# powersupply_grid8_0.net
KiCad netlist of a schematic drawn in Altium Designer
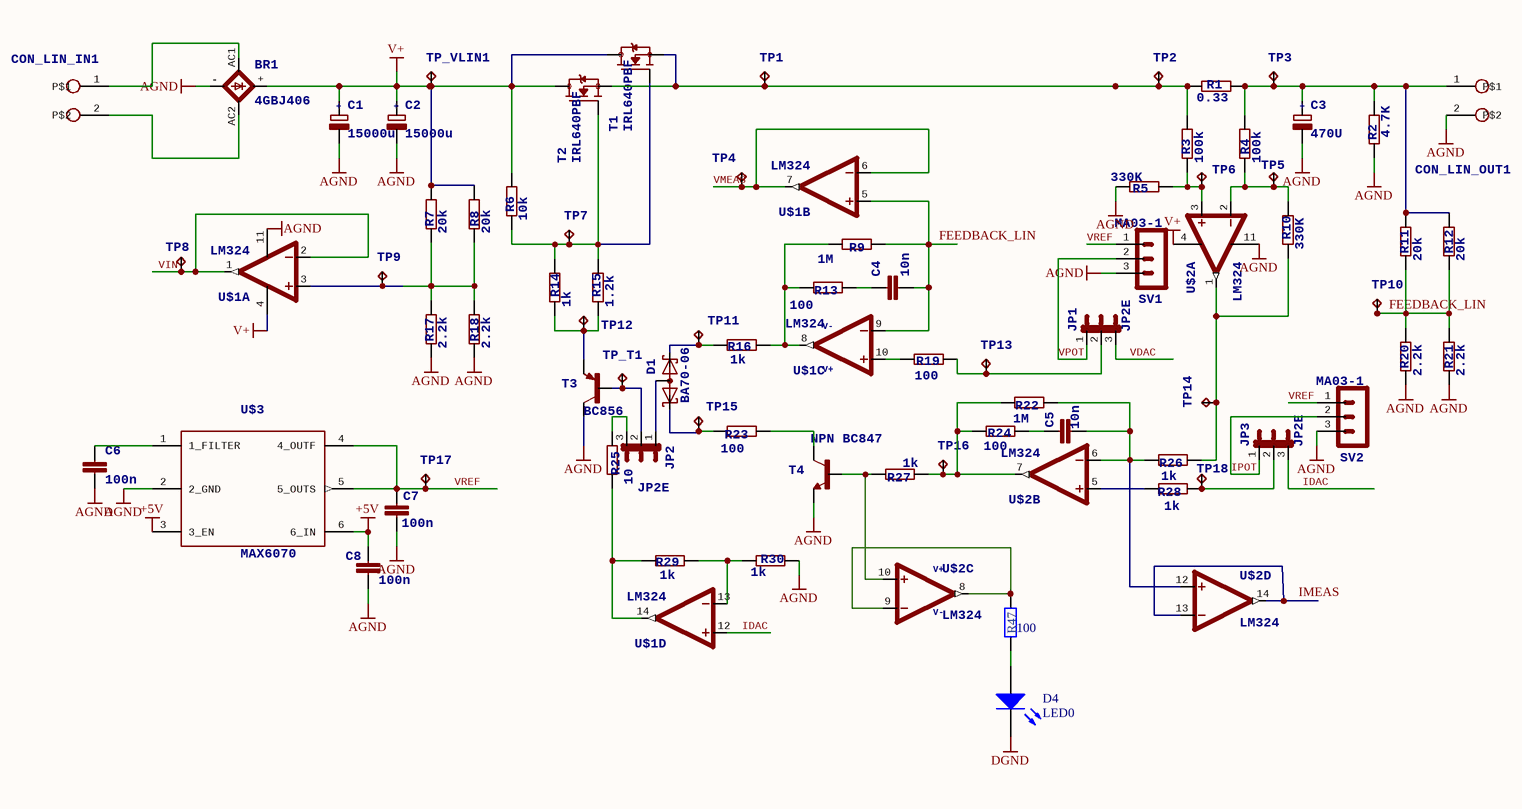
[diagram p0: powersupply_grid8_0.SchDoc]

(export (version "E")
  (design (tool "Eeschema 10.0.6"))
  (components
    (comp (ref "BR1") (value "4GBJ406") (footprint "FB100") (libsource (lib "4GBJ406F") (part "4GBJ406")))
    (comp (ref "C1")
      (value "15000u")
      (footprint "EB30D")
      (description "<B>POLARIZED CAPACITOR</B>, European symbol")
      (fields (field (name "+") "+"))
      (libsource (lib "rcl") (part "CPOL-EUE10-30"))
    )
    (comp (ref "C2")
      (value "15000u")
      (footprint "EB30D")
      (description "<B>POLARIZED CAPACITOR</B>, European symbol")
      (fields (field (name "+") "+"))
      (libsource (lib "rcl") (part "CPOL-EUE10-30"))
    )
    (comp (ref "C3")
      (value "470U")
      (footprint "E5-13")
      (description "<B>POLARIZED CAPACITOR</B>, European symbol")
      (fields (field (name "+") "+"))
      (libsource (lib "rcl") (part "CPOL-EUE5-13"))
    )
    (comp (ref "C4")
      (value "10n")
      (footprint "C0805")
      (description "<B>CAPACITOR</B>, European symbol")
      (libsource (lib "rcl") (part "C-EUC0805"))
    )
    (comp (ref "C5")
      (value "10n")
      (footprint "C0805")
      (description "<B>CAPACITOR</B>, European symbol")
      (libsource (lib "rcl") (part "C-EUC0805"))
    )
    (comp (ref "C6")
      (value "100n")
      (footprint "C0402")
      (description "<B>CAPACITOR</B>, European symbol")
      (libsource (lib "rcl") (part "C-EUC0402"))
    )
    (comp (ref "C7")
      (value "100n")
      (footprint "C0402")
      (description "<B>CAPACITOR</B>, European symbol")
      (libsource (lib "rcl") (part "C-EUC0402"))
    )
    (comp (ref "C8")
      (value "100n")
      (footprint "C0402")
      (description "<B>CAPACITOR</B>, European symbol")
      (libsource (lib "rcl") (part "C-EUC0402"))
    )
    (comp (ref "CON_LIN_IN1")
      (value "POWERCON")
      (footprint "MKS1852-6-0-202")
      (libsource (lib "powercon") (part "POWERCON"))
    )
    (comp (ref "CON_LIN_OUT1")
      (value "POWERCON")
      (footprint "MKS1852-6-0-202")
      (libsource (lib "powercon") (part "POWERCON"))
    )
    (comp (ref "D1") (value "BA70-06") (footprint "SOT23") (libsource (lib "diode") (part "BAS40-06")))
    (comp (ref "D4")
      (value "LED0")
      (footprint "LED-0")
      (description "Typical INFRARED GaAs LED")
      (fields (field (name "PUBLISHER") "Altium Limited"))
      (libsource (lib "Miscellaneous Devices") (part "LED0"))
    )
    (comp (ref "JP1")
      (value "JP2E")
      (footprint "JP2")
      (description "<b>JUMPER</b>")
      (libsource (lib "jumper") (part "JP2E"))
    )
    (comp (ref "JP2")
      (value "JP2E")
      (footprint "JP2")
      (description "<b>JUMPER</b>")
      (libsource (lib "jumper") (part "JP2E"))
    )
    (comp (ref "JP3")
      (value "JP2E")
      (footprint "JP2")
      (description "<b>JUMPER</b>")
      (libsource (lib "jumper") (part "JP2E"))
    )
    (comp (ref "R1")
      (value "0.33")
      (footprint "R2010")
      (description "<B>RESISTOR</B>, European symbol")
      (libsource (lib "rcl") (part "R-EU_R2010"))
    )
    (comp (ref "R2")
      (value "4.7K")
      (footprint "R2512")
      (description "<B>RESISTOR</B>, European symbol")
      (libsource (lib "rcl") (part "R-EU_R2512"))
    )
    (comp (ref "R3")
      (value "100k")
      (footprint "R0805")
      (description "<B>RESISTOR</B>, European symbol")
      (libsource (lib "rcl") (part "R-EU_R0805"))
    )
    (comp (ref "R4")
      (value "100k")
      (footprint "R0805")
      (description "<B>RESISTOR</B>, European symbol")
      (libsource (lib "rcl") (part "R-EU_R0805"))
    )
    (comp (ref "R5")
      (value "330K")
      (footprint "R0805")
      (description "<B>RESISTOR</B>, European symbol")
      (libsource (lib "rcl") (part "R-EU_R0805"))
    )
    (comp (ref "R6")
      (value "10k")
      (footprint "R0805")
      (description "<B>RESISTOR</B>, European symbol")
      (libsource (lib "rcl") (part "R-EU_R0805"))
    )
    (comp (ref "R7")
      (value "20k")
      (footprint "R0805")
      (description "<B>RESISTOR</B>, European symbol")
      (libsource (lib "rcl") (part "R-EU_R0805"))
    )
    (comp (ref "R8")
      (value "20k")
      (footprint "R0805")
      (description "<B>RESISTOR</B>, European symbol")
      (libsource (lib "rcl") (part "R-EU_R0805"))
    )
    (comp (ref "R9")
      (value "1M")
      (footprint "R0805")
      (description "<B>RESISTOR</B>, European symbol")
      (libsource (lib "rcl") (part "R-EU_R0805"))
    )
    (comp (ref "R10")
      (value "330K")
      (footprint "R0805")
      (description "<B>RESISTOR</B>, European symbol")
      (libsource (lib "rcl") (part "R-EU_R0805"))
    )
    (comp (ref "R11")
      (value "20k")
      (footprint "R0805")
      (description "<B>RESISTOR</B>, European symbol")
      (libsource (lib "rcl") (part "R-EU_R0805"))
    )
    (comp (ref "R12")
      (value "20k")
      (footprint "R0805")
      (description "<B>RESISTOR</B>, European symbol")
      (libsource (lib "rcl") (part "R-EU_R0805"))
    )
    (comp (ref "R13")
      (value "100")
      (footprint "R0805")
      (description "<B>RESISTOR</B>, European symbol")
      (libsource (lib "rcl") (part "R-EU_R0805"))
    )
    (comp (ref "R14")
      (value "1k")
      (footprint "R0805")
      (description "<B>RESISTOR</B>, European symbol")
      (libsource (lib "rcl") (part "R-EU_R0805"))
    )
    (comp (ref "R15")
      (value "1.2k")
      (footprint "R0805")
      (description "<B>RESISTOR</B>, European symbol")
      (libsource (lib "rcl") (part "R-EU_R0805"))
    )
    (comp (ref "R16")
      (value "1k")
      (footprint "R0805")
      (description "<B>RESISTOR</B>, European symbol")
      (libsource (lib "rcl") (part "R-EU_R0805"))
    )
    (comp (ref "R17")
      (value "2.2k")
      (footprint "R0805")
      (description "<B>RESISTOR</B>, European symbol")
      (libsource (lib "rcl") (part "R-EU_R0805"))
    )
    (comp (ref "R18")
      (value "2.2k")
      (footprint "R0805")
      (description "<B>RESISTOR</B>, European symbol")
      (libsource (lib "rcl") (part "R-EU_R0805"))
    )
    (comp (ref "R19")
      (value "100")
      (footprint "R0805")
      (description "<B>RESISTOR</B>, European symbol")
      (libsource (lib "rcl") (part "R-EU_R0805"))
    )
    (comp (ref "R20")
      (value "2.2k")
      (footprint "R0805")
      (description "<B>RESISTOR</B>, European symbol")
      (libsource (lib "rcl") (part "R-EU_R0805"))
    )
    (comp (ref "R21")
      (value "2.2k")
      (footprint "R0805")
      (description "<B>RESISTOR</B>, European symbol")
      (libsource (lib "rcl") (part "R-EU_R0805"))
    )
    (comp (ref "R22")
      (value "1M")
      (footprint "R0805")
      (description "<B>RESISTOR</B>, European symbol")
      (libsource (lib "rcl") (part "R-EU_R0805"))
    )
    (comp (ref "R23")
      (value "100")
      (footprint "R0805")
      (description "<B>RESISTOR</B>, European symbol")
      (libsource (lib "rcl") (part "R-EU_R0805"))
    )
    (comp (ref "R24")
      (value "100")
      (footprint "R0805")
      (description "<B>RESISTOR</B>, European symbol")
      (libsource (lib "rcl") (part "R-EU_R0805"))
    )
    (comp (ref "R25")
      (value "10")
      (footprint "R0805")
      (description "<B>RESISTOR</B>, European symbol")
      (libsource (lib "rcl") (part "R-EU_R0805"))
    )
    (comp (ref "R26")
      (value "1k")
      (footprint "R0805")
      (description "<B>RESISTOR</B>, European symbol")
      (libsource (lib "rcl") (part "R-EU_R0805"))
    )
    (comp (ref "R27")
      (value "1k")
      (footprint "R0805")
      (description "<B>RESISTOR</B>, European symbol")
      (libsource (lib "rcl") (part "R-EU_R0805"))
    )
    (comp (ref "R28")
      (value "1k")
      (footprint "R0805")
      (description "<B>RESISTOR</B>, European symbol")
      (libsource (lib "rcl") (part "R-EU_R0805"))
    )
    (comp (ref "R29")
      (value "1k")
      (footprint "R0805")
      (description "<B>RESISTOR</B>, European symbol")
      (libsource (lib "rcl") (part "R-EU_R0805"))
    )
    (comp (ref "R30")
      (value "1k")
      (footprint "R0805")
      (description "<B>RESISTOR</B>, European symbol")
      (libsource (lib "rcl") (part "R-EU_R0805"))
    )
    (comp (ref "R47")
      (value "100")
      (footprint "6-0805_L")
      (description "Resistor")
      (fields (field (name "Comment") "Res2") (field (name "PUBLISHER") "Altium Limited"))
      (libsource (lib "Miscellaneous Devices") (part "Res2"))
    )
    (comp (ref "SV1")
      (value "MA03-1")
      (footprint "MA03-1")
      (description "<b>PIN HEADER</b>")
      (libsource (lib "con-lstb") (part "MA03-1"))
    )
    (comp (ref "SV2")
      (value "MA03-1")
      (footprint "MA03-1")
      (description "<b>PIN HEADER</b>")
      (libsource (lib "con-lstb") (part "MA03-1"))
    )
    (comp (ref "T1")
      (value "IRL640PBF")
      (footprint "TO-220AB")
      (libsource (lib "TO-220AB") (part "IRL640PBF"))
    )
    (comp (ref "T2")
      (value "IRL640PBF")
      (footprint "TO-220AB")
      (libsource (lib "TO-220AB") (part "IRL640PBF"))
    )
    (comp (ref "T3")
      (value "BC856")
      (footprint "SOT23-BEC")
      (description "PNP Transistror")
      (libsource (lib "transistor") (part "*-PNP-SOT23-BEC"))
    )
    (comp (ref "T4")
      (value "NPN BC847")
      (footprint "SOT23-BEC")
      (libsource (lib "transistor") (part "*-NPN-SOT23-BEC"))
    )
    (comp (ref "TP1")
      (value "TPB2,54")
      (footprint "B2,54")
      (description "<b>Test pad</b>")
      (libsource (lib "testpad") (part "TPB2,54"))
    )
    (comp (ref "TP2")
      (value "TPB2,54")
      (footprint "B2,54")
      (description "<b>Test pad</b>")
      (libsource (lib "testpad") (part "TPB2,54"))
    )
    (comp (ref "TP3")
      (value "TPB2,54")
      (footprint "B2,54")
      (description "<b>Test pad</b>")
      (libsource (lib "testpad") (part "TPB2,54"))
    )
    (comp (ref "TP4")
      (value "TPB2,54")
      (footprint "B2,54")
      (description "<b>Test pad</b>")
      (libsource (lib "testpad") (part "TPB2,54"))
    )
    (comp (ref "TP5")
      (value "TPB2,54")
      (footprint "B2,54")
      (description "<b>Test pad</b>")
      (libsource (lib "testpad") (part "TPB2,54"))
    )
    (comp (ref "TP6")
      (value "TPB2,54")
      (footprint "B2,54")
      (description "<b>Test pad</b>")
      (libsource (lib "testpad") (part "TPB2,54"))
    )
    (comp (ref "TP7")
      (value "TPB2,54")
      (footprint "B2,54")
      (description "<b>Test pad</b>")
      (libsource (lib "testpad") (part "TPB2,54"))
    )
    (comp (ref "TP8")
      (value "TPB2,54")
      (footprint "B2,54")
      (description "<b>Test pad</b>")
      (libsource (lib "testpad") (part "TPB2,54"))
    )
    (comp (ref "TP9")
      (value "TPB2,54")
      (footprint "B2,54")
      (description "<b>Test pad</b>")
      (libsource (lib "testpad") (part "TPB2,54"))
    )
    (comp (ref "TP10")
      (value "TPB2,54")
      (footprint "B2,54")
      (description "<b>Test pad</b>")
      (libsource (lib "testpad") (part "TPB2,54"))
    )
    (comp (ref "TP11")
      (value "TPB2,54")
      (footprint "B2,54")
      (description "<b>Test pad</b>")
      (libsource (lib "testpad") (part "TPB2,54"))
    )
    (comp (ref "TP12")
      (value "TPB2,54")
      (footprint "B2,54")
      (description "<b>Test pad</b>")
      (libsource (lib "testpad") (part "TPB2,54"))
    )
    (comp (ref "TP13")
      (value "TPB2,54")
      (footprint "B2,54")
      (description "<b>Test pad</b>")
      (libsource (lib "testpad") (part "TPB2,54"))
    )
    (comp (ref "TP14")
      (value "TPB2,54")
      (footprint "B2,54")
      (description "<b>Test pad</b>")
      (libsource (lib "testpad") (part "TPB2,54"))
    )
    (comp (ref "TP15")
      (value "TPB2,54")
      (footprint "B2,54")
      (description "<b>Test pad</b>")
      (libsource (lib "testpad") (part "TPB2,54"))
    )
    (comp (ref "TP16")
      (value "TPB2,54")
      (footprint "B2,54")
      (description "<b>Test pad</b>")
      (libsource (lib "testpad") (part "TPB2,54"))
    )
    (comp (ref "TP17")
      (value "TPB2,54")
      (footprint "B2,54")
      (description "<b>Test pad</b>")
      (libsource (lib "testpad") (part "TPB2,54"))
    )
    (comp (ref "TP18")
      (value "TPB2,54")
      (footprint "B2,54")
      (description "<b>Test pad</b>")
      (libsource (lib "testpad") (part "TPB2,54"))
    )
    (comp (ref "TP_T1")
      (value "TPB2,54")
      (footprint "B2,54")
      (description "<b>Test pad</b>")
      (libsource (lib "testpad") (part "TPB2,54"))
    )
    (comp (ref "TP_VLIN1")
      (value "TPB2,54")
      (footprint "B2,54")
      (description "<b>Test pad</b>")
      (libsource (lib "testpad") (part "TPB2,54"))
    )
    (comp (ref "U$1")
      (value "LM324")
      (footprint "SO14")
      (fields (field (name "V+") "V+") (field (name "V-") "V-"))
      (libsource (lib "lm324") (part "LM324"))
    )
    (comp (ref "U$2")
      (value "LM324")
      (footprint "SO14")
      (fields (field (name "V+") "V+") (field (name "V-") "V-"))
      (libsource (lib "lm324") (part "LM324"))
    )
    (comp (ref "U$3") (value "MAX6070") (footprint "SOT23-6") (libsource (lib "max6070") (part "MAX6070")))
  )
  (nets
    (net (code "1") (name "+5V") (class "Default")
      (node (ref "C8") (pin "1") (pinfunction "1_1") (pintype "passive"))
      (node (ref "U$3") (pin "3") (pinfunction "3_EN_3") (pintype "passive"))
      (node (ref "U$3") (pin "6") (pinfunction "6_IN_6") (pintype "passive"))
    )
    (net (code "2") (name "/FEEDBACK_LIN") (class "Default")
      (node (ref "C4") (pin "2") (pinfunction "2_2") (pintype "passive"))
      (node (ref "R11") (pin "1") (pinfunction "1_1") (pintype "passive"))
      (node (ref "R12") (pin "1") (pinfunction "1_1") (pintype "passive"))
      (node (ref "R20") (pin "2") (pinfunction "2_2") (pintype "passive"))
      (node (ref "R21") (pin "2") (pinfunction "2_2") (pintype "passive"))
      (node (ref "R9") (pin "1") (pinfunction "1_1") (pintype "passive"))
      (node (ref "TP10") (pin "TP") (pinfunction "TP_TP") (pintype "passive"))
      (node (ref "U$1") (pin "5") (pinfunction "+IN_5") (pintype "passive"))
      (node (ref "U$1") (pin "9") (pinfunction "-IN_9") (pintype "passive"))
    )
    (net (code "3") (name "/IDAC") (class "Default")
      (node (ref "JP3") (pin "3") (pinfunction "3_3") (pintype "passive"))
      (node (ref "U$1") (pin "12") (pinfunction "+IN_12") (pintype "passive"))
    )
    (net (code "4") (name "/IMEAS") (class "Default")
      (node (ref "U$2") (pin "13") (pinfunction "-IN_13") (pintype "passive"))
      (node (ref "U$2") (pin "14") (pinfunction "OUT_14") (pintype "output"))
    )
    (net (code "5") (name "/IPOT") (class "Default")
      (node (ref "JP3") (pin "1") (pinfunction "1_1") (pintype "passive"))
      (node (ref "SV2") (pin "2") (pinfunction "2_2") (pintype "passive"))
    )
    (net (code "6") (name "/VDAC") (class "Default")
      (node (ref "JP1") (pin "3") (pinfunction "3_3") (pintype "passive"))
    )
    (net (code "7") (name "/VIN") (class "Default")
      (node (ref "TP8") (pin "TP") (pinfunction "TP_TP") (pintype "passive"))
      (node (ref "U$1") (pin "1") (pinfunction "OUT_1") (pintype "output"))
      (node (ref "U$1") (pin "2") (pinfunction "-IN_2") (pintype "passive"))
    )
    (net (code "8") (name "/VMEAS") (class "Default")
      (node (ref "TP4") (pin "TP") (pinfunction "TP_TP") (pintype "passive"))
      (node (ref "U$1") (pin "6") (pinfunction "-IN_6") (pintype "passive"))
      (node (ref "U$1") (pin "7") (pinfunction "OUT_7") (pintype "output"))
    )
    (net (code "9") (name "/VPOT") (class "Default")
      (node (ref "JP1") (pin "1") (pinfunction "1_1") (pintype "passive"))
      (node (ref "SV1") (pin "2") (pinfunction "2_2") (pintype "passive"))
    )
    (net (code "10") (name "/VREF") (class "Default")
      (node (ref "C7") (pin "1") (pinfunction "1_1") (pintype "passive"))
      (node (ref "SV1") (pin "1") (pinfunction "1_1") (pintype "passive"))
      (node (ref "SV2") (pin "1") (pinfunction "1_1") (pintype "passive"))
      (node (ref "TP17") (pin "TP") (pinfunction "TP_TP") (pintype "passive"))
      (node (ref "U$3") (pin "4") (pinfunction "4_OUTF_4") (pintype "passive"))
      (node (ref "U$3") (pin "5") (pinfunction "5_OUTS_5") (pintype "output"))
    )
    (net (code "11") (name "AGND") (class "Default")
      (node (ref "BR1") (pin "-") (pinfunction "-_-") (pintype "passive"))
      (node (ref "C1") (pin "-") (pinfunction "-_-") (pintype "passive"))
      (node (ref "C2") (pin "-") (pinfunction "-_-") (pintype "passive"))
      (node (ref "C3") (pin "-") (pinfunction "-_-") (pintype "passive"))
      (node (ref "C6") (pin "2") (pinfunction "2_2") (pintype "passive"))
      (node (ref "C7") (pin "2") (pinfunction "2_2") (pintype "passive"))
      (node (ref "C8") (pin "2") (pinfunction "2_2") (pintype "passive"))
      (node (ref "CON_LIN_OUT1") (pin "2") (pinfunction "P$2_2") (pintype "passive"))
      (node (ref "R17") (pin "1") (pinfunction "1_1") (pintype "passive"))
      (node (ref "R18") (pin "1") (pinfunction "1_1") (pintype "passive"))
      (node (ref "R2") (pin "1") (pinfunction "1_1") (pintype "passive"))
      (node (ref "R20") (pin "1") (pinfunction "1_1") (pintype "passive"))
      (node (ref "R21") (pin "1") (pinfunction "1_1") (pintype "passive"))
      (node (ref "R30") (pin "2") (pinfunction "2_2") (pintype "passive"))
      (node (ref "R5") (pin "2") (pinfunction "2_2") (pintype "passive"))
      (node (ref "SV1") (pin "3") (pinfunction "3_3") (pintype "passive"))
      (node (ref "SV2") (pin "3") (pinfunction "3_3") (pintype "passive"))
      (node (ref "T3") (pin "C") (pinfunction "C_C") (pintype "passive"))
      (node (ref "T4") (pin "E") (pinfunction "E_E") (pintype "passive"))
      (node (ref "U$1") (pin "11") (pinfunction "V-_11") (pintype "power_in"))
      (node (ref "U$2") (pin "11") (pinfunction "V-_11") (pintype "power_in"))
      (node (ref "U$3") (pin "2") (pinfunction "2_GND_2") (pintype "power_in"))
    )
    (net (code "12") (name "DGND") (class "Default")
      (node (ref "D4") (pin "2") (pinfunction "K_2") (pintype "passive"))
    )
    (net (code "13") (name "Net-(C4-Pad1)") (class "Default")
      (node (ref "C4") (pin "1") (pinfunction "1_1") (pintype "passive"))
      (node (ref "R13") (pin "1") (pinfunction "1_1") (pintype "passive"))
    )
    (net (code "14") (name "Net-(C5-Pad1)") (class "Default")
      (node (ref "C5") (pin "1") (pinfunction "1_1") (pintype "passive"))
      (node (ref "R24") (pin "1") (pinfunction "1_1") (pintype "passive"))
    )
    (net (code "15") (name "Net-(CON_LIN_IN1-P$1)") (class "Default")
      (node (ref "BR1") (pin "AC1") (pinfunction "AC1_AC1") (pintype "passive"))
      (node (ref "CON_LIN_IN1") (pin "1") (pinfunction "P$1_1") (pintype "passive"))
    )
    (net (code "16") (name "Net-(CON_LIN_IN1-P$2)") (class "Default")
      (node (ref "BR1") (pin "AC2") (pinfunction "AC2_AC2") (pintype "passive"))
      (node (ref "CON_LIN_IN1") (pin "2") (pinfunction "P$2_2") (pintype "passive"))
    )
    (net (code "17") (name "Net-(CON_LIN_OUT1-P$1)") (class "Default")
      (node (ref "C3") (pin "+") (pinfunction "+_+") (pintype "passive"))
      (node (ref "CON_LIN_OUT1") (pin "1") (pinfunction "P$1_1") (pintype "passive"))
      (node (ref "R1") (pin "2") (pinfunction "2_2") (pintype "passive"))
      (node (ref "R11") (pin "2") (pinfunction "2_2") (pintype "passive"))
      (node (ref "R12") (pin "2") (pinfunction "2_2") (pintype "passive"))
      (node (ref "R2") (pin "2") (pinfunction "2_2") (pintype "passive"))
      (node (ref "R4") (pin "2") (pinfunction "2_2") (pintype "passive"))
      (node (ref "TP3") (pin "TP") (pinfunction "TP_TP") (pintype "passive"))
    )
    (net (code "18") (name "Net-(D1-AA)") (class "Default")
      (node (ref "D1") (pin "3") (pinfunction "AA_3") (pintype "passive"))
      (node (ref "JP2") (pin "1") (pinfunction "1_1") (pintype "passive"))
    )
    (net (code "19") (name "Net-(D1-K1)") (class "Default")
      (node (ref "D1") (pin "1") (pinfunction "K1_1") (pintype "passive"))
      (node (ref "R23") (pin "2") (pinfunction "2_2") (pintype "passive"))
      (node (ref "TP15") (pin "TP") (pinfunction "TP_TP") (pintype "passive"))
    )
    (net (code "20") (name "Net-(D1-K2)") (class "Default")
      (node (ref "D1") (pin "2") (pinfunction "K2_2") (pintype "passive"))
      (node (ref "R16") (pin "2") (pinfunction "2_2") (pintype "passive"))
      (node (ref "TP11") (pin "TP") (pinfunction "TP_TP") (pintype "passive"))
    )
    (net (code "21") (name "Net-(D4-A)") (class "Default")
      (node (ref "D4") (pin "1") (pinfunction "A_1") (pintype "passive"))
      (node (ref "R47") (pin "2") (pinfunction "2_2") (pintype "passive"))
    )
    (net (code "22") (name "Net-(JP1-Pad2)") (class "Default")
      (node (ref "JP1") (pin "2") (pinfunction "2_2") (pintype "passive"))
      (node (ref "R19") (pin "1") (pinfunction "1_1") (pintype "passive"))
      (node (ref "TP13") (pin "TP") (pinfunction "TP_TP") (pintype "passive"))
    )
    (net (code "23") (name "Net-(JP2-Pad2)") (class "Default")
      (node (ref "JP2") (pin "2") (pinfunction "2_2") (pintype "passive"))
      (node (ref "T3") (pin "B") (pinfunction "B_B") (pintype "passive"))
      (node (ref "TP_T1") (pin "TP") (pinfunction "TP_TP") (pintype "passive"))
    )
    (net (code "24") (name "Net-(JP2-Pad3)") (class "Default")
      (node (ref "JP2") (pin "3") (pinfunction "3_3") (pintype "passive"))
      (node (ref "R25") (pin "1") (pinfunction "1_1") (pintype "passive"))
    )
    (net (code "25") (name "Net-(JP3-Pad2)") (class "Default")
      (node (ref "JP3") (pin "2") (pinfunction "2_2") (pintype "passive"))
      (node (ref "R28") (pin "1") (pinfunction "1_1") (pintype "passive"))
      (node (ref "TP18") (pin "TP") (pinfunction "TP_TP") (pintype "passive"))
    )
    (net (code "26") (name "Net-(R14-Pad1)") (class "Default")
      (node (ref "R14") (pin "1") (pinfunction "1_1") (pintype "passive"))
      (node (ref "R15") (pin "1") (pinfunction "1_1") (pintype "passive"))
      (node (ref "T3") (pin "E") (pinfunction "E_E") (pintype "passive"))
      (node (ref "TP12") (pin "TP") (pinfunction "TP_TP") (pintype "passive"))
    )
    (net (code "27") (name "Net-(R23-Pad1)") (class "Default")
      (node (ref "R23") (pin "1") (pinfunction "1_1") (pintype "passive"))
      (node (ref "T4") (pin "C") (pinfunction "C_C") (pintype "passive"))
    )
    (net (code "28") (name "Net-(T1-G)") (class "Default")
      (node (ref "R14") (pin "2") (pinfunction "2_2") (pintype "passive"))
      (node (ref "R15") (pin "2") (pinfunction "2_2") (pintype "passive"))
      (node (ref "R6") (pin "1") (pinfunction "1_1") (pintype "passive"))
      (node (ref "T1") (pin "P$1") (pinfunction "G_P$1") (pintype "passive"))
      (node (ref "T2") (pin "P$1") (pinfunction "G_P$1") (pintype "passive"))
      (node (ref "TP7") (pin "TP") (pinfunction "TP_TP") (pintype "passive"))
    )
    (net (code "29") (name "Net-(T1-S)") (class "Default")
      (node (ref "R1") (pin "1") (pinfunction "1_1") (pintype "passive"))
      (node (ref "R3") (pin "2") (pinfunction "2_2") (pintype "passive"))
      (node (ref "T1") (pin "P$3") (pinfunction "S_P$3") (pintype "passive"))
      (node (ref "T2") (pin "P$3") (pinfunction "S_P$3") (pintype "passive"))
      (node (ref "TP1") (pin "TP") (pinfunction "TP_TP") (pintype "passive"))
      (node (ref "TP2") (pin "TP") (pinfunction "TP_TP") (pintype "passive"))
    )
    (net (code "30") (name "Net-(U$1A-+IN)") (class "Default")
      (node (ref "R17") (pin "2") (pinfunction "2_2") (pintype "passive"))
      (node (ref "R18") (pin "2") (pinfunction "2_2") (pintype "passive"))
      (node (ref "R7") (pin "1") (pinfunction "1_1") (pintype "passive"))
      (node (ref "R8") (pin "1") (pinfunction "1_1") (pintype "passive"))
      (node (ref "TP9") (pin "TP") (pinfunction "TP_TP") (pintype "passive"))
      (node (ref "U$1") (pin "3") (pinfunction "+IN_3") (pintype "passive"))
    )
    (net (code "31") (name "Net-(U$1C-+IN)") (class "Default")
      (node (ref "R19") (pin "2") (pinfunction "2_2") (pintype "passive"))
      (node (ref "U$1") (pin "10") (pinfunction "+IN_10") (pintype "passive"))
    )
    (net (code "32") (name "Net-(U$1C-OUT)") (class "Default")
      (node (ref "R13") (pin "2") (pinfunction "2_2") (pintype "passive"))
      (node (ref "R16") (pin "1") (pinfunction "1_1") (pintype "passive"))
      (node (ref "R9") (pin "2") (pinfunction "2_2") (pintype "passive"))
      (node (ref "U$1") (pin "8") (pinfunction "OUT_8") (pintype "output"))
    )
    (net (code "33") (name "Net-(U$1D--IN)") (class "Default")
      (node (ref "R29") (pin "1") (pinfunction "1_1") (pintype "passive"))
      (node (ref "R30") (pin "1") (pinfunction "1_1") (pintype "passive"))
      (node (ref "U$1") (pin "13") (pinfunction "-IN_13") (pintype "passive"))
    )
    (net (code "34") (name "Net-(U$1D-OUT)") (class "Default")
      (node (ref "R25") (pin "2") (pinfunction "2_2") (pintype "passive"))
      (node (ref "R29") (pin "2") (pinfunction "2_2") (pintype "passive"))
      (node (ref "U$1") (pin "14") (pinfunction "OUT_14") (pintype "output"))
    )
    (net (code "35") (name "Net-(U$2A-+IN)") (class "Default")
      (node (ref "R3") (pin "1") (pinfunction "1_1") (pintype "passive"))
      (node (ref "R5") (pin "1") (pinfunction "1_1") (pintype "passive"))
      (node (ref "TP6") (pin "TP") (pinfunction "TP_TP") (pintype "passive"))
      (node (ref "U$2") (pin "3") (pinfunction "+IN_3") (pintype "passive"))
    )
    (net (code "36") (name "Net-(U$2A--IN)") (class "Default")
      (node (ref "R10") (pin "2") (pinfunction "2_2") (pintype "passive"))
      (node (ref "R4") (pin "1") (pinfunction "1_1") (pintype "passive"))
      (node (ref "TP5") (pin "TP") (pinfunction "TP_TP") (pintype "passive"))
      (node (ref "U$2") (pin "2") (pinfunction "-IN_2") (pintype "passive"))
    )
    (net (code "37") (name "Net-(U$2A-OUT)") (class "Default")
      (node (ref "R10") (pin "1") (pinfunction "1_1") (pintype "passive"))
      (node (ref "R26") (pin "1") (pinfunction "1_1") (pintype "passive"))
      (node (ref "TP14") (pin "TP") (pinfunction "TP_TP") (pintype "passive"))
      (node (ref "U$2") (pin "1") (pinfunction "OUT_1") (pintype "output"))
    )
    (net (code "38") (name "Net-(U$2B-+IN)") (class "Default")
      (node (ref "R28") (pin "2") (pinfunction "2_2") (pintype "passive"))
      (node (ref "U$2") (pin "5") (pinfunction "+IN_5") (pintype "passive"))
    )
    (net (code "39") (name "Net-(U$2B--IN)") (class "Default")
      (node (ref "C5") (pin "2") (pinfunction "2_2") (pintype "passive"))
      (node (ref "R22") (pin "1") (pinfunction "1_1") (pintype "passive"))
      (node (ref "R26") (pin "2") (pinfunction "2_2") (pintype "passive"))
      (node (ref "U$2") (pin "12") (pinfunction "+IN_12") (pintype "passive"))
      (node (ref "U$2") (pin "6") (pinfunction "-IN_6") (pintype "passive"))
    )
    (net (code "40") (name "Net-(U$2B-OUT)") (class "Default")
      (node (ref "R22") (pin "2") (pinfunction "2_2") (pintype "passive"))
      (node (ref "R24") (pin "2") (pinfunction "2_2") (pintype "passive"))
      (node (ref "R27") (pin "1") (pinfunction "1_1") (pintype "passive"))
      (node (ref "TP16") (pin "TP") (pinfunction "TP_TP") (pintype "passive"))
      (node (ref "U$2") (pin "7") (pinfunction "OUT_7") (pintype "output"))
    )
    (net (code "41") (name "Net-(U$2C-+IN)") (class "Default")
      (node (ref "R27") (pin "2") (pinfunction "2_2") (pintype "passive"))
      (node (ref "T4") (pin "B") (pinfunction "B_B") (pintype "passive"))
      (node (ref "U$2") (pin "10") (pinfunction "+IN_10") (pintype "passive"))
    )
    (net (code "42") (name "Net-(U$2C--IN)") (class "Default")
      (node (ref "R47") (pin "1") (pinfunction "1_1") (pintype "passive"))
      (node (ref "U$2") (pin "8") (pinfunction "OUT_8") (pintype "output"))
      (node (ref "U$2") (pin "9") (pinfunction "-IN_9") (pintype "passive"))
    )
    (net (code "43") (name "Net-(U$3-1_FILTER)") (class "Default")
      (node (ref "C6") (pin "1") (pinfunction "1_1") (pintype "passive"))
      (node (ref "U$3") (pin "1") (pinfunction "1_FILTER_1") (pintype "passive"))
    )
    (net (code "44") (name "V+") (class "Default")
      (node (ref "BR1") (pin "+") (pinfunction "+_+") (pintype "passive"))
      (node (ref "C1") (pin "+") (pinfunction "+_+") (pintype "passive"))
      (node (ref "C2") (pin "+") (pinfunction "+_+") (pintype "passive"))
      (node (ref "R6") (pin "2") (pinfunction "2_2") (pintype "passive"))
      (node (ref "R7") (pin "2") (pinfunction "2_2") (pintype "passive"))
      (node (ref "R8") (pin "2") (pinfunction "2_2") (pintype "passive"))
      (node (ref "T1") (pin "P$2") (pinfunction "D_P$2") (pintype "passive"))
      (node (ref "T2") (pin "P$2") (pinfunction "D_P$2") (pintype "passive"))
      (node (ref "TP_VLIN1") (pin "TP") (pinfunction "TP_TP") (pintype "passive"))
      (node (ref "U$1") (pin "4") (pinfunction "V+_4") (pintype "power_in"))
      (node (ref "U$2") (pin "4") (pinfunction "V+_4") (pintype "power_in"))
    )
  )
)
